# ADC_Input_protection.net
KiCad netlist of a schematic drawn in Altium Designer
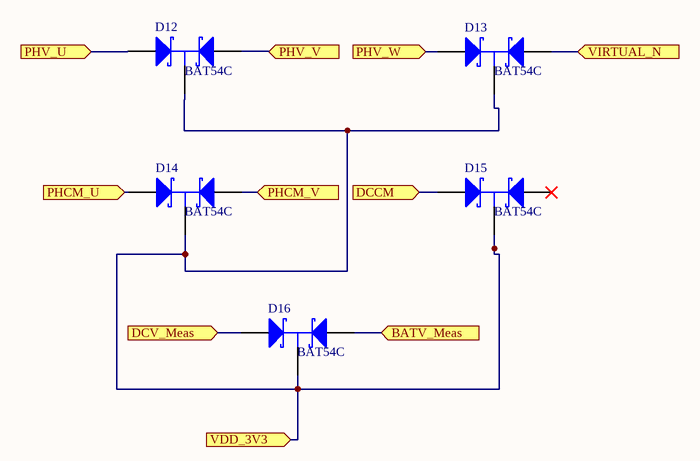
[diagram p0: ADC_Input_protection.SchDoc]

(export (version "E")
  (design (tool "Eeschema 10.0.6"))
  (components
    (comp (ref "D12")
      (value "BAT54C")
      (footprint "NXP-SOT23-3_V")
      (description "Schottky Barrier Diode, 30 V, 2 uA, -55 to 150 degC, 3-Pin SOT23, RoHS, Tape and Reel")
      (fields (field (name "MANUFACTURER") "NXP Semiconductors"))
      (libsource (lib "Altium Content Vault") (part "NXP-DSKY_A1A2K3-3"))
    )
    (comp (ref "D13")
      (value "BAT54C")
      (footprint "NXP-SOT23-3_V")
      (description "Schottky Barrier Diode, 30 V, 2 uA, -55 to 150 degC, 3-Pin SOT23, RoHS, Tape and Reel")
      (fields (field (name "MANUFACTURER") "NXP Semiconductors"))
      (libsource (lib "Altium Content Vault") (part "NXP-DSKY_A1A2K3-3"))
    )
    (comp (ref "D14")
      (value "BAT54C")
      (footprint "NXP-SOT23-3_V")
      (description "Schottky Barrier Diode, 30 V, 2 uA, -55 to 150 degC, 3-Pin SOT23, RoHS, Tape and Reel")
      (fields (field (name "MANUFACTURER") "NXP Semiconductors"))
      (libsource (lib "Altium Content Vault") (part "NXP-DSKY_A1A2K3-3"))
    )
    (comp (ref "D15")
      (value "BAT54C")
      (footprint "NXP-SOT23-3_V")
      (description "Schottky Barrier Diode, 30 V, 2 uA, -55 to 150 degC, 3-Pin SOT23, RoHS, Tape and Reel")
      (fields (field (name "MANUFACTURER") "NXP Semiconductors"))
      (libsource (lib "Altium Content Vault") (part "NXP-DSKY_A1A2K3-3"))
    )
    (comp (ref "D16")
      (value "BAT54C")
      (footprint "NXP-SOT23-3_V")
      (description "Schottky Barrier Diode, 30 V, 2 uA, -55 to 150 degC, 3-Pin SOT23, RoHS, Tape and Reel")
      (fields (field (name "MANUFACTURER") "NXP Semiconductors"))
      (libsource (lib "Altium Content Vault") (part "NXP-DSKY_A1A2K3-3"))
    )
  )
  (nets
    (net (code "1") (name "/BATV_Meas") (class "Default")
      (node (ref "D16") (pin "1") (pinfunction "A_1") (pintype "passive"))
    )
    (net (code "2") (name "/DCCM") (class "Default")
      (node (ref "D15") (pin "2") (pinfunction "A_2") (pintype "passive"))
    )
    (net (code "3") (name "/DCV_Meas") (class "Default")
      (node (ref "D16") (pin "2") (pinfunction "A_2") (pintype "passive"))
    )
    (net (code "4") (name "/PHCM_U") (class "Default")
      (node (ref "D14") (pin "2") (pinfunction "A_2") (pintype "passive"))
    )
    (net (code "5") (name "/PHCM_V") (class "Default")
      (node (ref "D14") (pin "1") (pinfunction "A_1") (pintype "passive"))
    )
    (net (code "6") (name "/PHV_U") (class "Default")
      (node (ref "D12") (pin "2") (pinfunction "A_2") (pintype "passive"))
    )
    (net (code "7") (name "/PHV_V") (class "Default")
      (node (ref "D12") (pin "1") (pinfunction "A_1") (pintype "passive"))
    )
    (net (code "8") (name "/PHV_W") (class "Default")
      (node (ref "D13") (pin "2") (pinfunction "A_2") (pintype "passive"))
    )
    (net (code "9") (name "/VDD_3V3") (class "Default")
      (node (ref "D12") (pin "3") (pinfunction "K_3") (pintype "passive"))
      (node (ref "D13") (pin "3") (pinfunction "K_3") (pintype "passive"))
      (node (ref "D14") (pin "3") (pinfunction "K_3") (pintype "passive"))
      (node (ref "D15") (pin "3") (pinfunction "K_3") (pintype "passive"))
      (node (ref "D16") (pin "3") (pinfunction "K_3") (pintype "passive"))
    )
    (net (code "10") (name "/VIRTUAL_N") (class "Default")
      (node (ref "D13") (pin "1") (pinfunction "A_1") (pintype "passive"))
    )
    (net (code "11") (name "unconnected-(D15-A-Pad1)") (class "Default")
      (node (ref "D15") (pin "1") (pinfunction "A_1") (pintype "passive+no_connect"))
    )
  )
)
